# LED_Strip.net
KiCad netlist of a schematic drawn in EAGLE
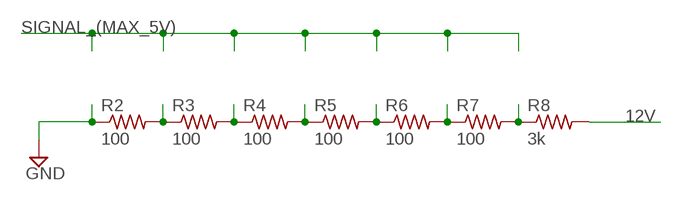
[diagram p0: schematic, sheet 1]

(export (version "E")
  (design (tool "Eeschema 10.0.6"))
  (components
    (comp (ref "R2")
      (value "100")
      (footprint "eagle-import:R0603")
      (libsource (lib "eagle-import") (part "R-US_R0603"))
    )
    (comp (ref "R3")
      (value "100")
      (footprint "eagle-import:R0603")
      (libsource (lib "eagle-import") (part "R-US_R0603"))
    )
    (comp (ref "R4")
      (value "100")
      (footprint "eagle-import:R0603")
      (libsource (lib "eagle-import") (part "R-US_R0603"))
    )
    (comp (ref "R5")
      (value "100")
      (footprint "eagle-import:R0603")
      (libsource (lib "eagle-import") (part "R-US_R0603"))
    )
    (comp (ref "R6")
      (value "100")
      (footprint "eagle-import:R0603")
      (libsource (lib "eagle-import") (part "R-US_R0603"))
    )
    (comp (ref "R7")
      (value "100")
      (footprint "eagle-import:R0603")
      (libsource (lib "eagle-import") (part "R-US_R0603"))
    )
    (comp (ref "R8")
      (value "3k")
      (footprint "eagle-import:R0603")
      (libsource (lib "eagle-import") (part "R-US_R0603"))
    )
  )
  (nets
    (net (code "1") (name "/12V") (class "Default")
      (node (ref "R8") (pin "2") (pinfunction "2_2") (pintype "passive"))
    )
    (net (code "3") (name "GND") (class "Default")
      (node (ref "R2") (pin "1") (pinfunction "1_1") (pintype "passive"))
    )
    (net (code "4") (name "Net-(R2-Pad2)") (class "Default")
      (node (ref "R2") (pin "2") (pinfunction "2_2") (pintype "passive"))
      (node (ref "R3") (pin "1") (pinfunction "1_1") (pintype "passive"))
    )
    (net (code "5") (name "Net-(R3-Pad2)") (class "Default")
      (node (ref "R3") (pin "2") (pinfunction "2_2") (pintype "passive"))
      (node (ref "R4") (pin "1") (pinfunction "1_1") (pintype "passive"))
    )
    (net (code "6") (name "Net-(R4-Pad2)") (class "Default")
      (node (ref "R4") (pin "2") (pinfunction "2_2") (pintype "passive"))
      (node (ref "R5") (pin "1") (pinfunction "1_1") (pintype "passive"))
    )
    (net (code "7") (name "Net-(R5-Pad2)") (class "Default")
      (node (ref "R5") (pin "2") (pinfunction "2_2") (pintype "passive"))
      (node (ref "R6") (pin "1") (pinfunction "1_1") (pintype "passive"))
    )
    (net (code "8") (name "Net-(R6-Pad2)") (class "Default")
      (node (ref "R6") (pin "2") (pinfunction "2_2") (pintype "passive"))
      (node (ref "R7") (pin "1") (pinfunction "1_1") (pintype "passive"))
    )
    (net (code "9") (name "Net-(R7-Pad2)") (class "Default")
      (node (ref "R7") (pin "2") (pinfunction "2_2") (pintype "passive"))
      (node (ref "R8") (pin "1") (pinfunction "1_1") (pintype "passive"))
    )
  )
)
